# Secret_Knock.net
KiCad netlist of a schematic drawn in EAGLE
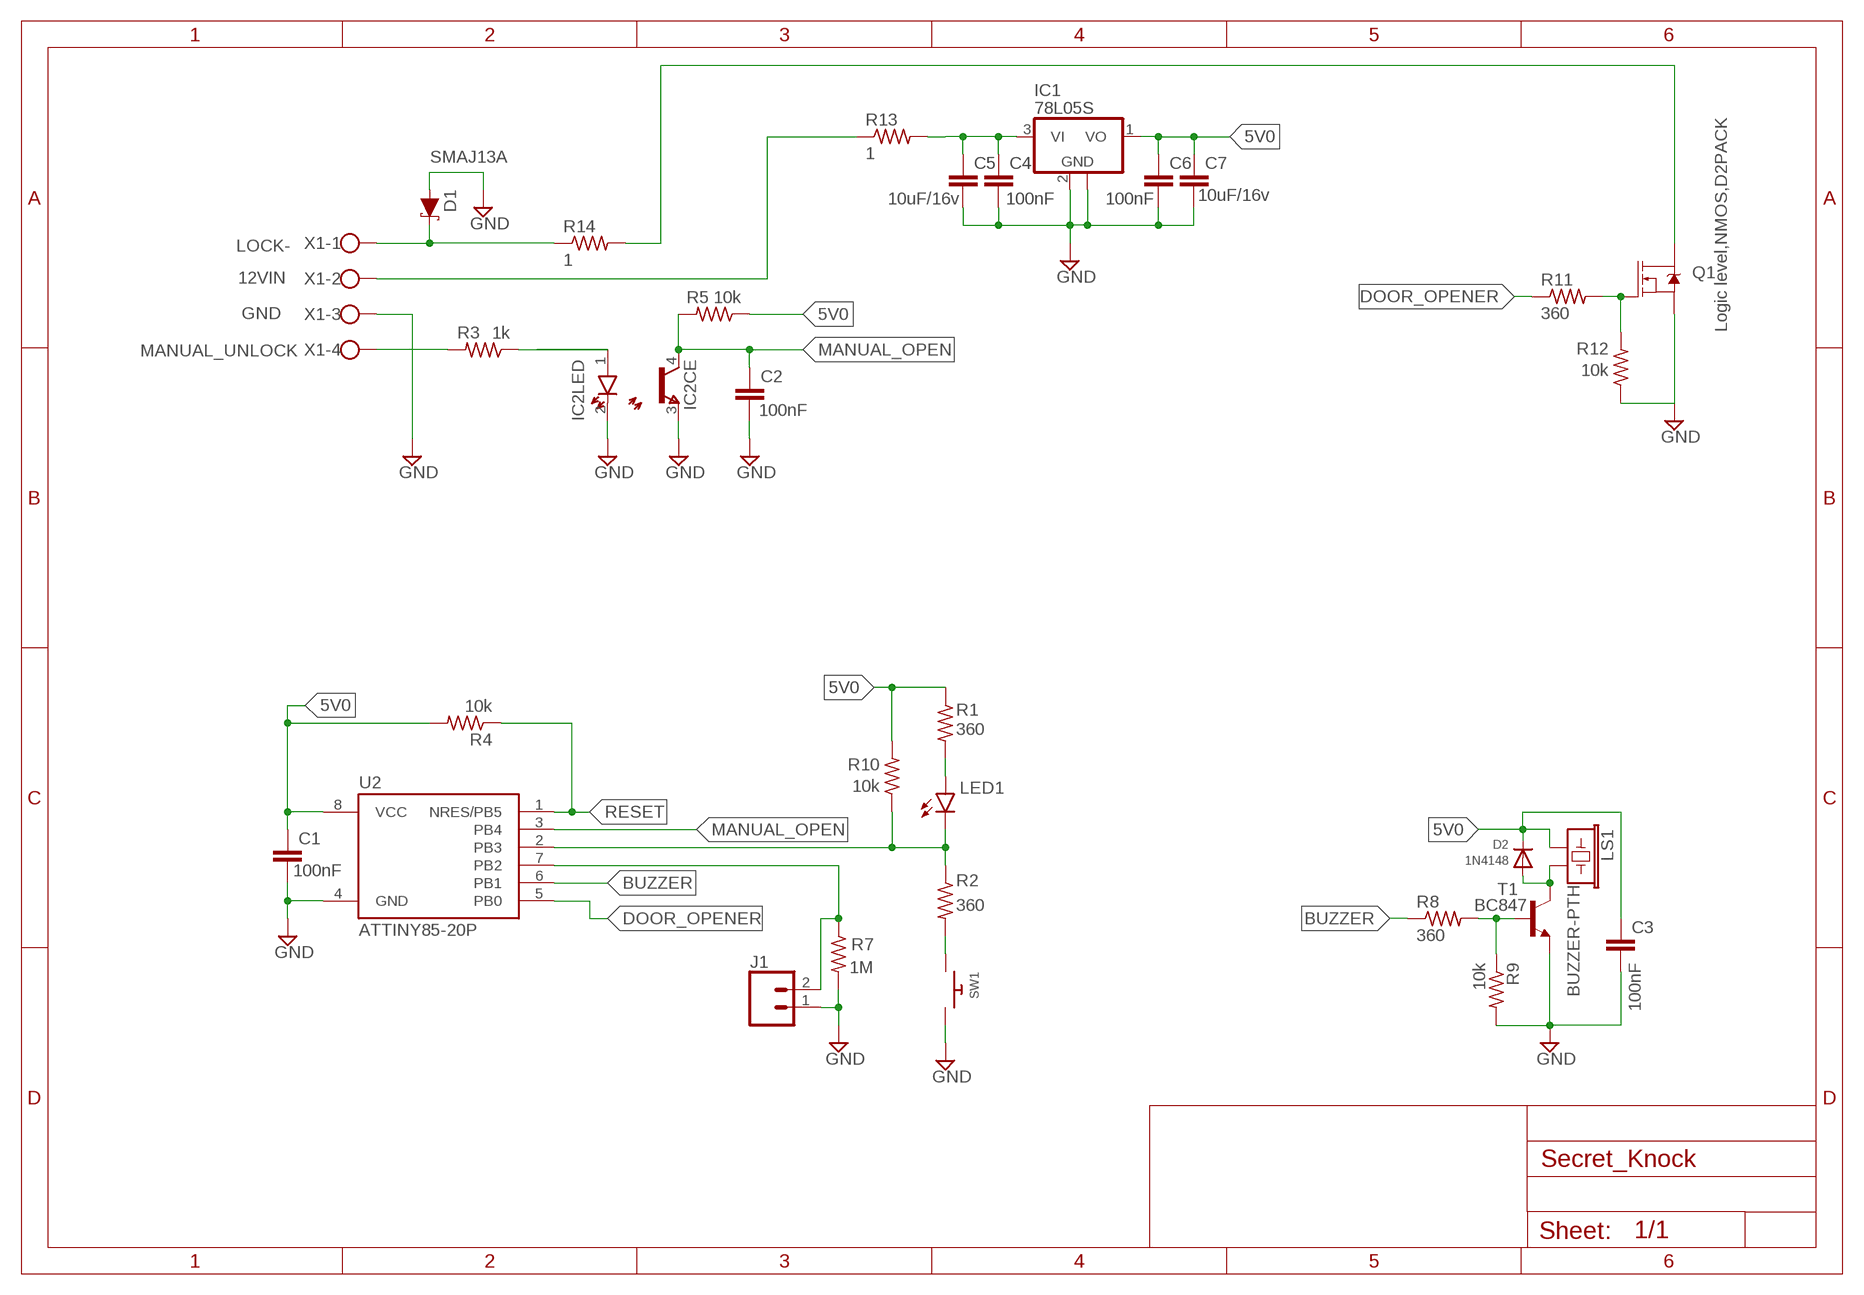
[diagram p0: schematic, sheet 1]

(export (version "E")
  (design (tool "Eeschema 10.0.6"))
  (components
    (comp (ref "C1")
      (value "100nF")
      (footprint "eagle-import:C0805")
      (libsource (lib "eagle-import") (part "C-EUC0805"))
    )
    (comp (ref "C2")
      (value "100nF")
      (footprint "eagle-import:C0805")
      (libsource (lib "eagle-import") (part "C-EUC0805"))
    )
    (comp (ref "C3")
      (value "100nF")
      (footprint "eagle-import:C0805")
      (libsource (lib "eagle-import") (part "C-EUC0805"))
    )
    (comp (ref "C4")
      (value "100nF")
      (footprint "eagle-import:C0805")
      (libsource (lib "eagle-import") (part "C-EUC0805"))
    )
    (comp (ref "C5")
      (value "10uF/16v")
      (footprint "eagle-import:C0805")
      (libsource (lib "eagle-import") (part "C-EUC0805"))
    )
    (comp (ref "C6")
      (value "100nF")
      (footprint "eagle-import:C0805")
      (libsource (lib "eagle-import") (part "C-EUC0805"))
    )
    (comp (ref "C7")
      (value "10uF/16v")
      (footprint "eagle-import:C0805")
      (libsource (lib "eagle-import") (part "C-EUC0805"))
    )
    (comp (ref "D1")
      (value "SMAJ13A")
      (footprint "eagle-import:SMA-DIODE")
      (libsource (lib "eagle-import") (part "DIODE-SCHOTTKY-SS14"))
    )
    (comp (ref "D2")
      (value "1N4148")
      (footprint "eagle-import:SOD-123")
      (libsource (lib "eagle-import") (part "DIODESOD-123"))
    )
    (comp (ref "IC1")
      (value "78L05S")
      (footprint "eagle-import:SOT89")
      (libsource (lib "eagle-import") (part "78LF08"))
    )
    (comp (ref "IC2")
      (value "GENERIC OPTOCOUPLER, PC817")
      (footprint "eagle-import:SFH")
      (fields (field (name "MF") "VISHAY/TELEFUNKEN") (field (name "MPN") "SFH6156-4T"))
      (libsource (lib "eagle-import") (part "SFH6156"))
    )
    (comp (ref "J1")
      (value "CONN_02POLAR_LOCK")
      (footprint "eagle-import:MOLEX-1X2_LOCK")
      (libsource (lib "eagle-import") (part "CONN_02POLAR_LOCK"))
    )
    (comp (ref "LED1")
      (value "LEDSML0805")
      (footprint "eagle-import:SML0805")
      (libsource (lib "eagle-import") (part "LEDSML0805"))
    )
    (comp (ref "LS1")
      (value "BUZZER-PTH")
      (footprint "eagle-import:BUZZER-12MM")
      (libsource (lib "eagle-import") (part "BUZZER-PTH"))
    )
    (comp (ref "Q1")
      (value "Logic level,NMOS,D2PACK")
      (footprint "eagle-import:TO-263_D2PAK")
      (libsource (lib "eagle-import") (part "MOSFET-NCH-PSMN7R0"))
    )
    (comp (ref "R1")
      (value "360")
      (footprint "eagle-import:R0805")
      (libsource (lib "eagle-import") (part "R-US_R0805"))
    )
    (comp (ref "R2")
      (value "360")
      (footprint "eagle-import:R0805")
      (libsource (lib "eagle-import") (part "R-US_R0805"))
    )
    (comp (ref "R3")
      (value "1k")
      (footprint "eagle-import:R0805")
      (libsource (lib "eagle-import") (part "R-US_R0805"))
    )
    (comp (ref "R4")
      (value "10k")
      (footprint "eagle-import:R0805")
      (libsource (lib "eagle-import") (part "R-US_R0805"))
    )
    (comp (ref "R5")
      (value "10k")
      (footprint "eagle-import:R0805")
      (libsource (lib "eagle-import") (part "R-US_R0805"))
    )
    (comp (ref "R7")
      (value "1M")
      (footprint "eagle-import:R0805")
      (libsource (lib "eagle-import") (part "R-US_R0805"))
    )
    (comp (ref "R8")
      (value "360")
      (footprint "eagle-import:R0805")
      (libsource (lib "eagle-import") (part "R-US_R0805"))
    )
    (comp (ref "R9")
      (value "10k")
      (footprint "eagle-import:R0805")
      (libsource (lib "eagle-import") (part "R-US_R0805"))
    )
    (comp (ref "R10")
      (value "10k")
      (footprint "eagle-import:R0805")
      (libsource (lib "eagle-import") (part "R-US_R0805"))
    )
    (comp (ref "R11")
      (value "360")
      (footprint "eagle-import:R0805")
      (libsource (lib "eagle-import") (part "R-US_R0805"))
    )
    (comp (ref "R12")
      (value "10k")
      (footprint "eagle-import:R0805")
      (libsource (lib "eagle-import") (part "R-US_R0805"))
    )
    (comp (ref "R13")
      (value "1")
      (footprint "eagle-import:R0805")
      (libsource (lib "eagle-import") (part "R-US_R0805"))
    )
    (comp (ref "R14")
      (value "1")
      (footprint "eagle-import:R0805")
      (libsource (lib "eagle-import") (part "R-US_R0805"))
    )
    (comp (ref "SW1")
      (value "SWITCH_PUSHBUTTONEVQ-PE")
      (footprint "eagle-import:TACT_PANA-EVQ")
      (libsource (lib "eagle-import") (part "SWITCH_PUSHBUTTONEVQ-PE"))
    )
    (comp (ref "T1")
      (value "BC847")
      (footprint "eagle-import:SOT23")
      (libsource (lib "eagle-import") (part "BC847"))
    )
    (comp (ref "U2")
      (value "ATTINY85-20P")
      (footprint "eagle-import:PDIP08_300MIL")
      (libsource (lib "eagle-import") (part "ATTINY85P-20"))
    )
    (comp (ref "X1")
      (value "W237-4")
      (footprint "eagle-import:W237-4")
      (libsource (lib "eagle-import") (part "W237-4"))
    )
  )
  (nets
    (net (code "1") (name "5V0") (class "Default")
      (node (ref "C1") (pin "1") (pinfunction "1_1") (pintype "passive"))
      (node (ref "C3") (pin "1") (pinfunction "1_1") (pintype "passive"))
      (node (ref "C6") (pin "1") (pinfunction "1_1") (pintype "passive"))
      (node (ref "C7") (pin "1") (pinfunction "1_1") (pintype "passive"))
      (node (ref "D2") (pin "C") (pinfunction "C_C") (pintype "passive"))
      (node (ref "IC1") (pin "1") (pinfunction "VO_1") (pintype "passive"))
      (node (ref "LS1") (pin "+") (pinfunction "1_+") (pintype "passive"))
      (node (ref "R1") (pin "1") (pinfunction "1_1") (pintype "passive"))
      (node (ref "R10") (pin "2") (pinfunction "2_2") (pintype "passive"))
      (node (ref "R4") (pin "2") (pinfunction "2_2") (pintype "passive"))
      (node (ref "R5") (pin "1") (pinfunction "1_1") (pintype "passive"))
      (node (ref "U2") (pin "8") (pinfunction "VCC_8") (pintype "power_in"))
    )
    (net (code "2") (name "BUZZER") (class "Default")
      (node (ref "R8") (pin "1") (pinfunction "1_1") (pintype "passive"))
      (node (ref "U2") (pin "6") (pinfunction "PB1_6") (pintype "bidirectional"))
    )
    (net (code "3") (name "DOOR_OPENER") (class "Default")
      (node (ref "R11") (pin "1") (pinfunction "1_1") (pintype "passive"))
      (node (ref "U2") (pin "5") (pinfunction "PB0_5") (pintype "bidirectional"))
    )
    (net (code "4") (name "GND") (class "Default")
      (node (ref "C1") (pin "2") (pinfunction "2_2") (pintype "passive"))
      (node (ref "C2") (pin "2") (pinfunction "2_2") (pintype "passive"))
      (node (ref "C3") (pin "2") (pinfunction "2_2") (pintype "passive"))
      (node (ref "C4") (pin "2") (pinfunction "2_2") (pintype "passive"))
      (node (ref "C5") (pin "2") (pinfunction "2_2") (pintype "passive"))
      (node (ref "C6") (pin "2") (pinfunction "2_2") (pintype "passive"))
      (node (ref "C7") (pin "2") (pinfunction "2_2") (pintype "passive"))
      (node (ref "D1") (pin "A") (pinfunction "A_A") (pintype "passive"))
      (node (ref "IC1") (pin "2") (pinfunction "GND_2") (pintype "passive"))
      (node (ref "IC1") (pin "2@1") (pinfunction "GND_2@1") (pintype "passive"))
      (node (ref "IC2") (pin "2") (pinfunction "K_2") (pintype "bidirectional"))
      (node (ref "IC2") (pin "3") (pinfunction "E_3") (pintype "bidirectional"))
      (node (ref "J1") (pin "1") (pinfunction "1_1") (pintype "passive"))
      (node (ref "Q1") (pin "3") (pinfunction "S_3") (pintype "bidirectional"))
      (node (ref "R12") (pin "1") (pinfunction "1_1") (pintype "passive"))
      (node (ref "R7") (pin "2") (pinfunction "2_2") (pintype "passive"))
      (node (ref "R9") (pin "2") (pinfunction "2_2") (pintype "passive"))
      (node (ref "SW1") (pin "P$2") (pinfunction "P$2_P$2") (pintype "passive"))
      (node (ref "T1") (pin "2") (pinfunction "E_2") (pintype "passive"))
      (node (ref "U2") (pin "4") (pinfunction "GND_4") (pintype "power_in"))
      (node (ref "X1") (pin "3") (pinfunction "KL_3") (pintype "passive"))
    )
    (net (code "5") (name "MANUAL_OPEN") (class "Default")
      (node (ref "C2") (pin "1") (pinfunction "1_1") (pintype "passive"))
      (node (ref "IC2") (pin "4") (pinfunction "C_4") (pintype "bidirectional"))
      (node (ref "R5") (pin "2") (pinfunction "2_2") (pintype "passive"))
      (node (ref "U2") (pin "3") (pinfunction "PB4_3") (pintype "bidirectional"))
    )
    (net (code "6") (name "Net-(IC1-VI)") (class "Default")
      (node (ref "C4") (pin "1") (pinfunction "1_1") (pintype "passive"))
      (node (ref "C5") (pin "1") (pinfunction "1_1") (pintype "passive"))
      (node (ref "IC1") (pin "3") (pinfunction "VI_3") (pintype "input"))
      (node (ref "R13") (pin "2") (pinfunction "2_2") (pintype "passive"))
    )
    (net (code "7") (name "Net-(IC2B-A)") (class "Default")
      (node (ref "IC2") (pin "1") (pinfunction "A_1") (pintype "bidirectional"))
      (node (ref "R3") (pin "1") (pinfunction "1_1") (pintype "passive"))
    )
    (net (code "8") (name "Net-(LED1-PadA)") (class "Default")
      (node (ref "LED1") (pin "A") (pinfunction "A_A") (pintype "passive"))
      (node (ref "R1") (pin "2") (pinfunction "2_2") (pintype "passive"))
    )
    (net (code "9") (name "Net-(LS1-2)") (class "Default")
      (node (ref "D2") (pin "A") (pinfunction "A_A") (pintype "passive"))
      (node (ref "LS1") (pin "-") (pinfunction "2_-") (pintype "passive"))
      (node (ref "T1") (pin "3") (pinfunction "C_3") (pintype "passive"))
    )
    (net (code "10") (name "Net-(Q1-D)") (class "Default")
      (node (ref "Q1") (pin "2") (pinfunction "D_2") (pintype "bidirectional"))
      (node (ref "R14") (pin "2") (pinfunction "2_2") (pintype "passive"))
    )
    (net (code "11") (name "Net-(Q1-G)") (class "Default")
      (node (ref "Q1") (pin "1") (pinfunction "G_1") (pintype "bidirectional"))
      (node (ref "R11") (pin "2") (pinfunction "2_2") (pintype "passive"))
      (node (ref "R12") (pin "2") (pinfunction "2_2") (pintype "passive"))
    )
    (net (code "12") (name "Net-(R2-Pad2)") (class "Default")
      (node (ref "R2") (pin "2") (pinfunction "2_2") (pintype "passive"))
      (node (ref "SW1") (pin "P$1") (pinfunction "P$1_P$1") (pintype "passive"))
    )
    (net (code "13") (name "Net-(T1-B)") (class "Default")
      (node (ref "R8") (pin "2") (pinfunction "2_2") (pintype "passive"))
      (node (ref "R9") (pin "1") (pinfunction "1_1") (pintype "passive"))
      (node (ref "T1") (pin "1") (pinfunction "B_1") (pintype "passive"))
    )
    (net (code "14") (name "Net-(U2-PB2)") (class "Default")
      (node (ref "J1") (pin "2") (pinfunction "2_2") (pintype "passive"))
      (node (ref "R7") (pin "1") (pinfunction "1_1") (pintype "passive"))
      (node (ref "U2") (pin "7") (pinfunction "PB2_7") (pintype "bidirectional"))
    )
    (net (code "15") (name "Net-(U2-PB3)") (class "Default")
      (node (ref "LED1") (pin "C") (pinfunction "C_C") (pintype "passive"))
      (node (ref "R10") (pin "1") (pinfunction "1_1") (pintype "passive"))
      (node (ref "R2") (pin "1") (pinfunction "1_1") (pintype "passive"))
      (node (ref "U2") (pin "2") (pinfunction "PB3_2") (pintype "bidirectional"))
    )
    (net (code "16") (name "Net-(X1A-KL)") (class "Default")
      (node (ref "D1") (pin "C") (pinfunction "C_C") (pintype "passive"))
      (node (ref "R14") (pin "1") (pinfunction "1_1") (pintype "passive"))
      (node (ref "X1") (pin "1") (pinfunction "KL_1") (pintype "passive"))
    )
    (net (code "17") (name "Net-(X1B-KL)") (class "Default")
      (node (ref "R13") (pin "1") (pinfunction "1_1") (pintype "passive"))
      (node (ref "X1") (pin "2") (pinfunction "KL_2") (pintype "passive"))
    )
    (net (code "18") (name "Net-(X1D-KL)") (class "Default")
      (node (ref "R3") (pin "2") (pinfunction "2_2") (pintype "passive"))
      (node (ref "X1") (pin "4") (pinfunction "KL_4") (pintype "passive"))
    )
    (net (code "19") (name "RESET") (class "Default")
      (node (ref "R4") (pin "1") (pinfunction "1_1") (pintype "passive"))
      (node (ref "U2") (pin "1") (pinfunction "NRES/PB5_1") (pintype "bidirectional"))
    )
  )
)
